# hotmetal.net
KiCad netlist of a schematic drawn in EAGLE
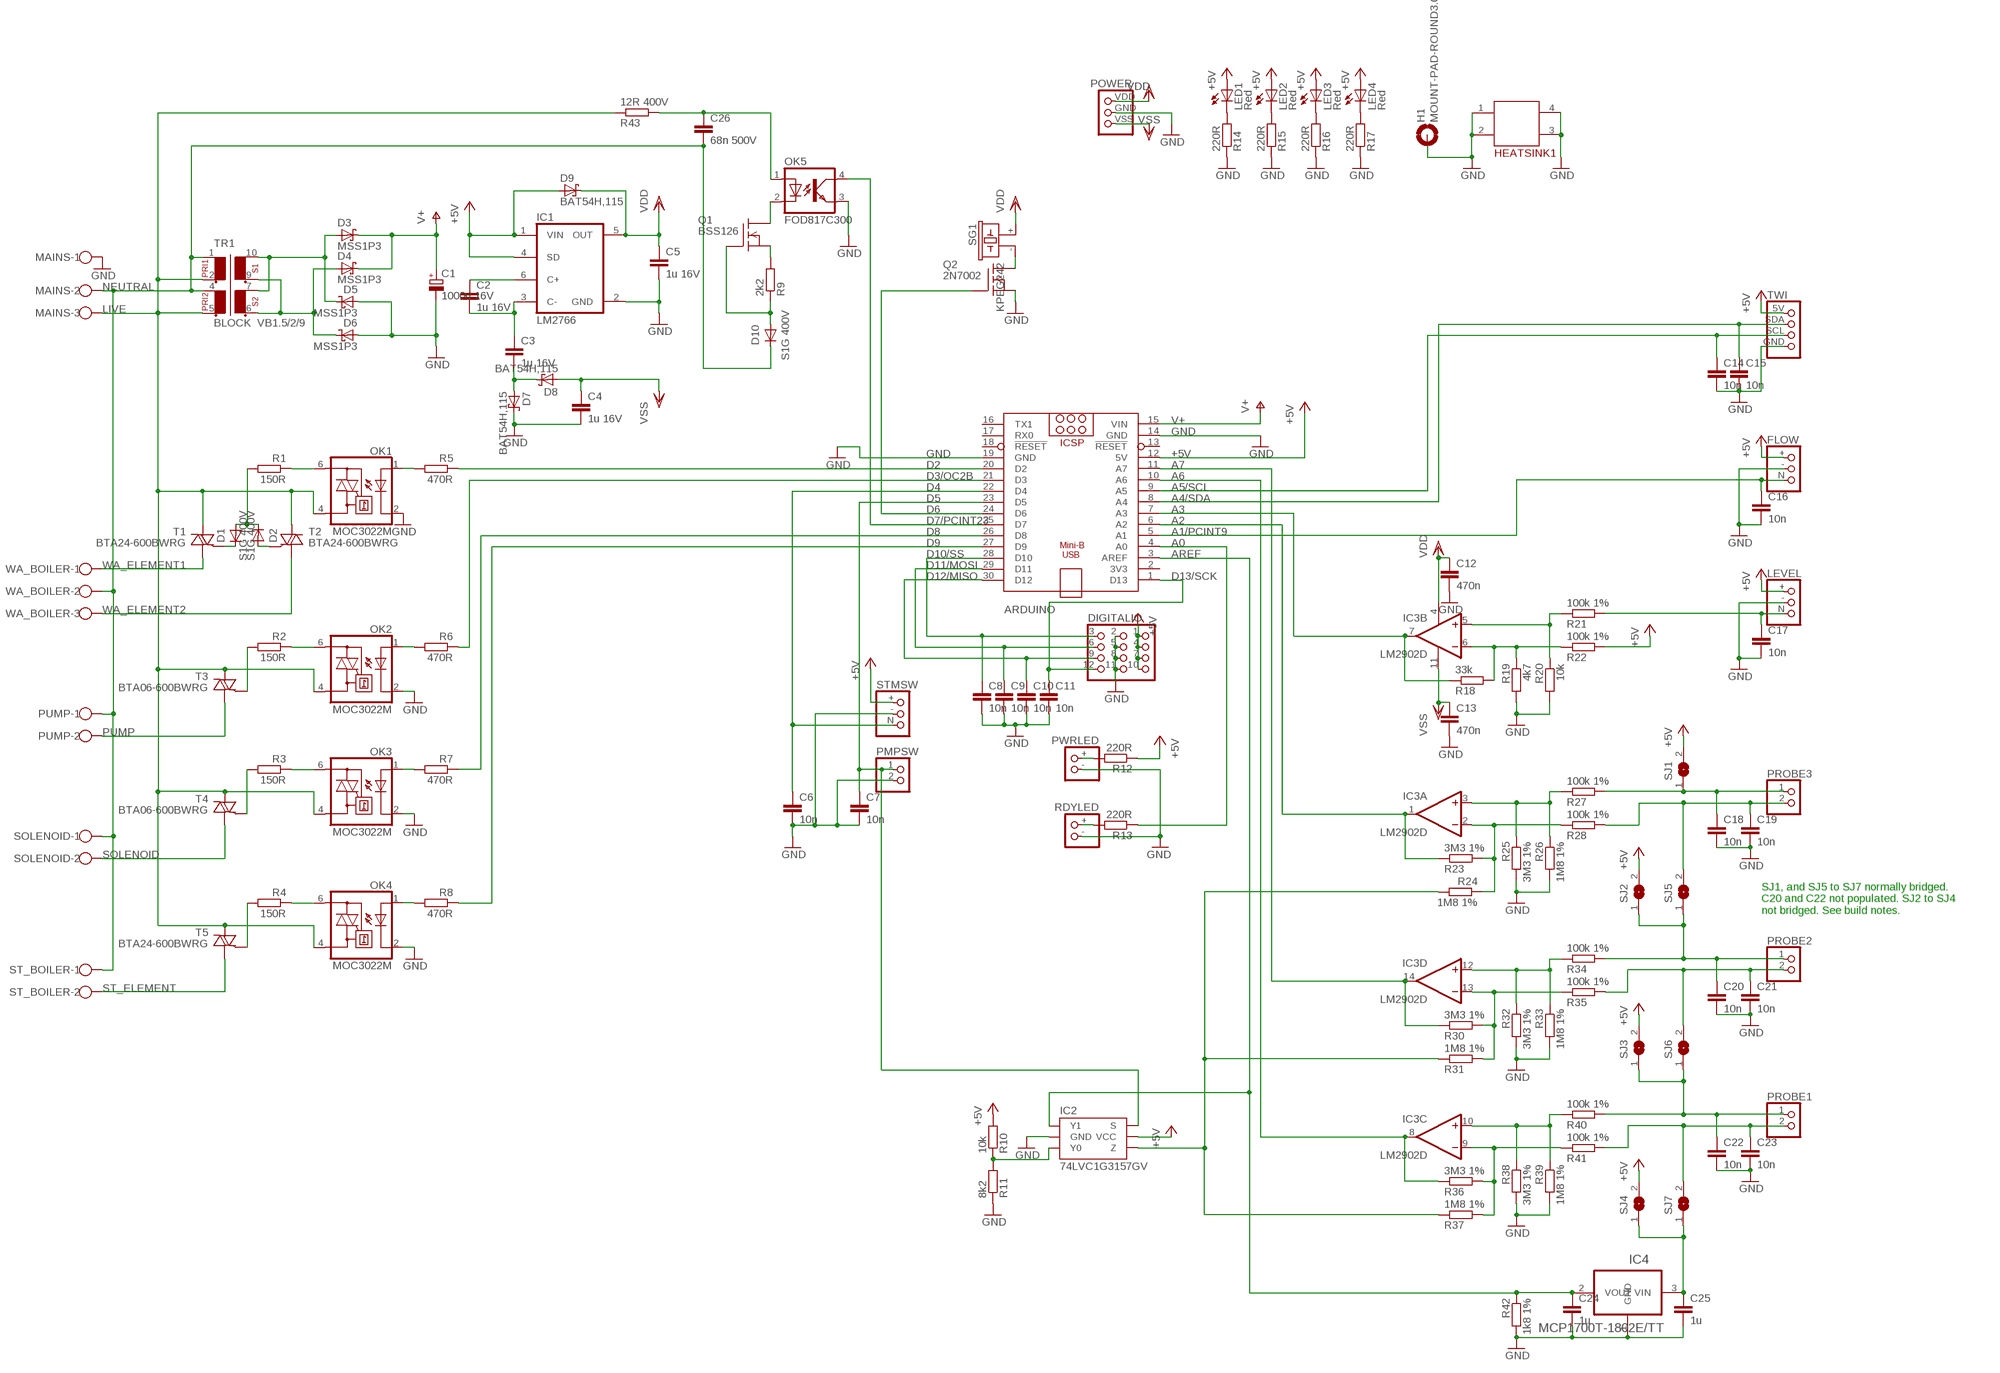
[diagram p0: schematic, sheet 1]

(export (version "E")
  (design (tool "Eeschema 10.0.6"))
  (components
    (comp (ref "ARDUINO")
      (value "ARDUINO_NANO")
      (footprint "eagle-import:ARDUINO_NANO")
      (libsource (lib "eagle-import") (part "ARDUINO_NANO"))
    )
    (comp (ref "C1")
      (value "1000u 16V")
      (footprint "eagle-import:E5-10,5")
      (libsource (lib "eagle-import") (part "CPOL-EUE5-10.5"))
    )
    (comp (ref "C2")
      (value "1u 16V")
      (footprint "eagle-import:C0603K")
      (libsource (lib "eagle-import") (part "C-EUC0603K"))
    )
    (comp (ref "C3")
      (value "1u 16V")
      (footprint "eagle-import:C0603K")
      (libsource (lib "eagle-import") (part "C-EUC0603K"))
    )
    (comp (ref "C4")
      (value "1u 16V")
      (footprint "eagle-import:C0603K")
      (libsource (lib "eagle-import") (part "C-EUC0603K"))
    )
    (comp (ref "C5")
      (value "1u 16V")
      (footprint "eagle-import:C0603K")
      (libsource (lib "eagle-import") (part "C-EUC0603K"))
    )
    (comp (ref "C6")
      (value "10n")
      (footprint "eagle-import:C0603K")
      (libsource (lib "eagle-import") (part "C-EUC0603K"))
    )
    (comp (ref "C7")
      (value "10n")
      (footprint "eagle-import:C0603K")
      (libsource (lib "eagle-import") (part "C-EUC0603K"))
    )
    (comp (ref "C8")
      (value "10n")
      (footprint "eagle-import:C0603K")
      (libsource (lib "eagle-import") (part "C-EUC0603K"))
    )
    (comp (ref "C9")
      (value "10n")
      (footprint "eagle-import:C0603K")
      (libsource (lib "eagle-import") (part "C-EUC0603K"))
    )
    (comp (ref "C10")
      (value "10n")
      (footprint "eagle-import:C0603K")
      (libsource (lib "eagle-import") (part "C-EUC0603K"))
    )
    (comp (ref "C11")
      (value "10n")
      (footprint "eagle-import:C0603K")
      (libsource (lib "eagle-import") (part "C-EUC0603K"))
    )
    (comp (ref "C12")
      (value "470n")
      (footprint "eagle-import:C0603K")
      (libsource (lib "eagle-import") (part "C-EUC0603K"))
    )
    (comp (ref "C13")
      (value "470n")
      (footprint "eagle-import:C0603K")
      (libsource (lib "eagle-import") (part "C-EUC0603K"))
    )
    (comp (ref "C14")
      (value "10n")
      (footprint "eagle-import:C0603K")
      (libsource (lib "eagle-import") (part "C-EUC0603K"))
    )
    (comp (ref "C15")
      (value "10n")
      (footprint "eagle-import:C0603K")
      (libsource (lib "eagle-import") (part "C-EUC0603K"))
    )
    (comp (ref "C16")
      (value "10n")
      (footprint "eagle-import:C0603K")
      (libsource (lib "eagle-import") (part "C-EUC0603K"))
    )
    (comp (ref "C17")
      (value "10n")
      (footprint "eagle-import:C0603K")
      (libsource (lib "eagle-import") (part "C-EUC0603K"))
    )
    (comp (ref "C18")
      (value "10n")
      (footprint "eagle-import:C0603K")
      (libsource (lib "eagle-import") (part "C-EUC0603K"))
    )
    (comp (ref "C19")
      (value "10n")
      (footprint "eagle-import:C0603K")
      (libsource (lib "eagle-import") (part "C-EUC0603K"))
    )
    (comp (ref "C20")
      (value "10n")
      (footprint "eagle-import:C0603K")
      (libsource (lib "eagle-import") (part "C-EUC0603K"))
    )
    (comp (ref "C21")
      (value "10n")
      (footprint "eagle-import:C0603K")
      (libsource (lib "eagle-import") (part "C-EUC0603K"))
    )
    (comp (ref "C22")
      (value "10n")
      (footprint "eagle-import:C0603K")
      (libsource (lib "eagle-import") (part "C-EUC0603K"))
    )
    (comp (ref "C23")
      (value "10n")
      (footprint "eagle-import:C0603K")
      (libsource (lib "eagle-import") (part "C-EUC0603K"))
    )
    (comp (ref "C24")
      (value "1u")
      (footprint "eagle-import:C0603K")
      (libsource (lib "eagle-import") (part "C-EUC0603K"))
    )
    (comp (ref "C25")
      (value "1u")
      (footprint "eagle-import:C0603K")
      (libsource (lib "eagle-import") (part "C-EUC0603K"))
    )
    (comp (ref "C26")
      (value "68n 500V")
      (footprint "eagle-import:C1210K")
      (libsource (lib "eagle-import") (part "C-EUC1210K"))
    )
    (comp (ref "D1")
      (value "S1G 400V")
      (footprint "eagle-import:DO214AC")
      (libsource (lib "eagle-import") (part "DIODE-DO214AC"))
    )
    (comp (ref "D2")
      (value "S1G 400V")
      (footprint "eagle-import:DO214AC")
      (libsource (lib "eagle-import") (part "DIODE-DO214AC"))
    )
    (comp (ref "D3")
      (value "MSS1P3")
      (footprint "eagle-import:POWERDI323")
      (libsource (lib "eagle-import") (part "PD3S160"))
    )
    (comp (ref "D4")
      (value "MSS1P3")
      (footprint "eagle-import:POWERDI323")
      (libsource (lib "eagle-import") (part "PD3S160"))
    )
    (comp (ref "D5")
      (value "MSS1P3")
      (footprint "eagle-import:POWERDI323")
      (libsource (lib "eagle-import") (part "PD3S160"))
    )
    (comp (ref "D6")
      (value "MSS1P3")
      (footprint "eagle-import:POWERDI323")
      (libsource (lib "eagle-import") (part "PD3S160"))
    )
    (comp (ref "D7")
      (value "BAT54H,115")
      (footprint "eagle-import:SOD123F")
      (libsource (lib "eagle-import") (part "BAT54H,115"))
    )
    (comp (ref "D8")
      (value "BAT54H,115")
      (footprint "eagle-import:SOD123F")
      (libsource (lib "eagle-import") (part "BAT54H,115"))
    )
    (comp (ref "D9")
      (value "BAT54H,115")
      (footprint "eagle-import:SOD123F")
      (libsource (lib "eagle-import") (part "BAT54H,115"))
    )
    (comp (ref "D10")
      (value "S1G 400V")
      (footprint "eagle-import:DO214AC")
      (libsource (lib "eagle-import") (part "DIODE-DO214AC"))
    )
    (comp (ref "DIGITALIO")
      (value "HDR4X3PWR")
      (footprint "eagle-import:HDR4X3PWR")
      (libsource (lib "eagle-import") (part "HDR4X3PWR"))
    )
    (comp (ref "FLOW")
      (value "HDR3PWR")
      (footprint "eagle-import:HDR3PWR")
      (libsource (lib "eagle-import") (part "HDR3PWR"))
    )
    (comp (ref "H1")
      (value "MOUNT-PAD-ROUND3.0")
      (footprint "eagle-import:3,0-PAD")
      (libsource (lib "eagle-import") (part "MOUNT-PAD-ROUND3.0"))
    )
    (comp (ref "HEATSINK1")
      (value "HOTMETALHEATSINK")
      (footprint "eagle-import:HOTMETALHEATSINK")
      (libsource (lib "eagle-import") (part "HOTMETALHEATSINK"))
    )
    (comp (ref "IC1")
      (value "LM2766")
      (footprint "eagle-import:SOT23-6")
      (libsource (lib "eagle-import") (part "LM2766"))
    )
    (comp (ref "IC2")
      (value "74LVC1G3157GV")
      (footprint "eagle-import:SOT457")
      (libsource (lib "eagle-import") (part "74LVC1G3157GV"))
    )
    (comp (ref "IC3")
      (value "LM2902D")
      (footprint "eagle-import:SO14")
      (libsource (lib "eagle-import") (part "LM2902D"))
    )
    (comp (ref "IC4")
      (value "MCP1700T-1802E/TT")
      (footprint "eagle-import:SOT23")
      (libsource (lib "eagle-import") (part "MCP1700T-1802E/TT"))
    )
    (comp (ref "LED1")
      (value "Red")
      (footprint "eagle-import:SML0805")
      (libsource (lib "eagle-import") (part "LEDSML0805"))
    )
    (comp (ref "LED2")
      (value "Red")
      (footprint "eagle-import:SML0805")
      (libsource (lib "eagle-import") (part "LEDSML0805"))
    )
    (comp (ref "LED3")
      (value "Red")
      (footprint "eagle-import:SML0805")
      (libsource (lib "eagle-import") (part "LEDSML0805"))
    )
    (comp (ref "LED4")
      (value "Red")
      (footprint "eagle-import:SML0805")
      (libsource (lib "eagle-import") (part "LEDSML0805"))
    )
    (comp (ref "LEVEL")
      (value "HDR3PWR")
      (footprint "eagle-import:HDR3PWR")
      (libsource (lib "eagle-import") (part "HDR3PWR"))
    )
    (comp (ref "MAINS")
      (value "W237-103")
      (footprint "eagle-import:W237-103")
      (fields (field (name "MPN") "237-103"))
      (libsource (lib "eagle-import") (part "W237-103"))
    )
    (comp (ref "OK1")
      (value "MOC3022M")
      (footprint "eagle-import:DIL06")
      (fields (field (name "MF") "FAIRCHILD SEMICONDUCTOR") (field (name "MPN") "MOC3022-M"))
      (libsource (lib "eagle-import") (part "MOC30M22"))
    )
    (comp (ref "OK2")
      (value "MOC3022M")
      (footprint "eagle-import:DIL06")
      (fields (field (name "MF") "FAIRCHILD SEMICONDUCTOR") (field (name "MPN") "MOC3022-M"))
      (libsource (lib "eagle-import") (part "MOC30M22"))
    )
    (comp (ref "OK3")
      (value "MOC3022M")
      (footprint "eagle-import:DIL06")
      (fields (field (name "MF") "FAIRCHILD SEMICONDUCTOR") (field (name "MPN") "MOC3022-M"))
      (libsource (lib "eagle-import") (part "MOC30M22"))
    )
    (comp (ref "OK4")
      (value "MOC3022M")
      (footprint "eagle-import:DIL06")
      (fields (field (name "MF") "FAIRCHILD SEMICONDUCTOR") (field (name "MPN") "MOC3022-M"))
      (libsource (lib "eagle-import") (part "MOC30M22"))
    )
    (comp (ref "OK5")
      (value "FOD817C300")
      (footprint "eagle-import:DIL04")
      (fields (field (name "MPN") "PC817X4J000F"))
      (libsource (lib "eagle-import") (part "PC817"))
    )
    (comp (ref "PMPSW")
      (value "HDR2")
      (footprint "eagle-import:HDR2")
      (libsource (lib "eagle-import") (part "HDR2"))
    )
    (comp (ref "POWER")
      (value "HDR3VDDVSS")
      (footprint "eagle-import:HDR2VDDVSS")
      (libsource (lib "eagle-import") (part "HDR3VDDVSS"))
    )
    (comp (ref "PROBE1")
      (value "HDR2")
      (footprint "eagle-import:HDR2")
      (libsource (lib "eagle-import") (part "HDR2"))
    )
    (comp (ref "PROBE2")
      (value "HDR2")
      (footprint "eagle-import:HDR2")
      (libsource (lib "eagle-import") (part "HDR2"))
    )
    (comp (ref "PROBE3")
      (value "HDR2")
      (footprint "eagle-import:HDR2")
      (libsource (lib "eagle-import") (part "HDR2"))
    )
    (comp (ref "PUMP")
      (value "W237-102")
      (footprint "eagle-import:W237-102")
      (fields (field (name "MPN") "237-102"))
      (libsource (lib "eagle-import") (part "W237-102"))
    )
    (comp (ref "PWRLED")
      (value "HDR2PWR")
      (footprint "eagle-import:HDR2PWR")
      (libsource (lib "eagle-import") (part "HDR2PWR"))
    )
    (comp (ref "Q1")
      (value "BSS126")
      (footprint "eagle-import:SOT23")
      (libsource (lib "eagle-import") (part "2N7002"))
    )
    (comp (ref "Q2")
      (value "2N7002")
      (footprint "eagle-import:SOT23")
      (libsource (lib "eagle-import") (part "2N7002"))
    )
    (comp (ref "R1")
      (value "150R")
      (footprint "eagle-import:0204_7")
      (libsource (lib "eagle-import") (part "R-EU_0204/7"))
    )
    (comp (ref "R2")
      (value "150R")
      (footprint "eagle-import:0204_7")
      (libsource (lib "eagle-import") (part "R-EU_0204/7"))
    )
    (comp (ref "R3")
      (value "150R")
      (footprint "eagle-import:0204_7")
      (libsource (lib "eagle-import") (part "R-EU_0204/7"))
    )
    (comp (ref "R4")
      (value "150R")
      (footprint "eagle-import:0204_7")
      (libsource (lib "eagle-import") (part "R-EU_0204/7"))
    )
    (comp (ref "R5")
      (value "470R")
      (footprint "eagle-import:R0805")
      (libsource (lib "eagle-import") (part "R-EU_R0805"))
    )
    (comp (ref "R6")
      (value "470R")
      (footprint "eagle-import:R0805")
      (libsource (lib "eagle-import") (part "R-EU_R0805"))
    )
    (comp (ref "R7")
      (value "470R")
      (footprint "eagle-import:R0805")
      (libsource (lib "eagle-import") (part "R-EU_R0805"))
    )
    (comp (ref "R8")
      (value "470R")
      (footprint "eagle-import:R0805")
      (libsource (lib "eagle-import") (part "R-EU_R0805"))
    )
    (comp (ref "R9")
      (value "2k2")
      (footprint "eagle-import:R0805")
      (libsource (lib "eagle-import") (part "R-EU_R0805"))
    )
    (comp (ref "R10")
      (value "10k")
      (footprint "eagle-import:R0805")
      (libsource (lib "eagle-import") (part "R-EU_R0805"))
    )
    (comp (ref "R11")
      (value "8k2")
      (footprint "eagle-import:R0805")
      (libsource (lib "eagle-import") (part "R-EU_R0805"))
    )
    (comp (ref "R12")
      (value "220R")
      (footprint "eagle-import:R0805")
      (libsource (lib "eagle-import") (part "R-EU_R0805"))
    )
    (comp (ref "R13")
      (value "220R")
      (footprint "eagle-import:R0805")
      (libsource (lib "eagle-import") (part "R-EU_R0805"))
    )
    (comp (ref "R14")
      (value "220R")
      (footprint "eagle-import:R0805")
      (libsource (lib "eagle-import") (part "R-EU_R0805"))
    )
    (comp (ref "R15")
      (value "220R")
      (footprint "eagle-import:R0805")
      (libsource (lib "eagle-import") (part "R-EU_R0805"))
    )
    (comp (ref "R16")
      (value "220R")
      (footprint "eagle-import:R0805")
      (libsource (lib "eagle-import") (part "R-EU_R0805"))
    )
    (comp (ref "R17")
      (value "220R")
      (footprint "eagle-import:R0805")
      (libsource (lib "eagle-import") (part "R-EU_R0805"))
    )
    (comp (ref "R18")
      (value "33k")
      (footprint "eagle-import:R0805")
      (libsource (lib "eagle-import") (part "R-EU_R0805"))
    )
    (comp (ref "R19")
      (value "4k7")
      (footprint "eagle-import:R0805")
      (libsource (lib "eagle-import") (part "R-EU_R0805"))
    )
    (comp (ref "R20")
      (value "10k")
      (footprint "eagle-import:R0805")
      (libsource (lib "eagle-import") (part "R-EU_R0805"))
    )
    (comp (ref "R21")
      (value "100k 1%")
      (footprint "eagle-import:R0805")
      (libsource (lib "eagle-import") (part "R-EU_R0805"))
    )
    (comp (ref "R22")
      (value "100k 1%")
      (footprint "eagle-import:R0805")
      (libsource (lib "eagle-import") (part "R-EU_R0805"))
    )
    (comp (ref "R23")
      (value "3M3 1%")
      (footprint "eagle-import:R0805")
      (libsource (lib "eagle-import") (part "R-EU_R0805"))
    )
    (comp (ref "R24")
      (value "1M8 1%")
      (footprint "eagle-import:R0805")
      (libsource (lib "eagle-import") (part "R-EU_R0805"))
    )
    (comp (ref "R25")
      (value "3M3 1%")
      (footprint "eagle-import:R0805")
      (libsource (lib "eagle-import") (part "R-EU_R0805"))
    )
    (comp (ref "R26")
      (value "1M8 1%")
      (footprint "eagle-import:R0805")
      (libsource (lib "eagle-import") (part "R-EU_R0805"))
    )
    (comp (ref "R27")
      (value "100k 1%")
      (footprint "eagle-import:R0805")
      (libsource (lib "eagle-import") (part "R-EU_R0805"))
    )
    (comp (ref "R28")
      (value "100k 1%")
      (footprint "eagle-import:R0805")
      (libsource (lib "eagle-import") (part "R-EU_R0805"))
    )
    (comp (ref "R30")
      (value "3M3 1%")
      (footprint "eagle-import:R0805")
      (libsource (lib "eagle-import") (part "R-EU_R0805"))
    )
    (comp (ref "R31")
      (value "1M8 1%")
      (footprint "eagle-import:R0805")
      (libsource (lib "eagle-import") (part "R-EU_R0805"))
    )
    (comp (ref "R32")
      (value "3M3 1%")
      (footprint "eagle-import:R0805")
      (libsource (lib "eagle-import") (part "R-EU_R0805"))
    )
    (comp (ref "R33")
      (value "1M8 1%")
      (footprint "eagle-import:R0805")
      (libsource (lib "eagle-import") (part "R-EU_R0805"))
    )
    (comp (ref "R34")
      (value "100k 1%")
      (footprint "eagle-import:R0805")
      (libsource (lib "eagle-import") (part "R-EU_R0805"))
    )
    (comp (ref "R35")
      (value "100k 1%")
      (footprint "eagle-import:R0805")
      (libsource (lib "eagle-import") (part "R-EU_R0805"))
    )
    (comp (ref "R36")
      (value "3M3 1%")
      (footprint "eagle-import:R0805")
      (libsource (lib "eagle-import") (part "R-EU_R0805"))
    )
    (comp (ref "R37")
      (value "1M8 1%")
      (footprint "eagle-import:R0805")
      (libsource (lib "eagle-import") (part "R-EU_R0805"))
    )
    (comp (ref "R38")
      (value "3M3 1%")
      (footprint "eagle-import:R0805")
      (libsource (lib "eagle-import") (part "R-EU_R0805"))
    )
    (comp (ref "R39")
      (value "1M8 1%")
      (footprint "eagle-import:R0805")
      (libsource (lib "eagle-import") (part "R-EU_R0805"))
    )
    (comp (ref "R40")
      (value "100k 1%")
      (footprint "eagle-import:R0805")
      (libsource (lib "eagle-import") (part "R-EU_R0805"))
    )
    (comp (ref "R41")
      (value "100k 1%")
      (footprint "eagle-import:R0805")
      (libsource (lib "eagle-import") (part "R-EU_R0805"))
    )
    (comp (ref "R42")
      (value "1k8 1%")
      (footprint "eagle-import:R0805")
      (libsource (lib "eagle-import") (part "R-EU_R0805"))
    )
    (comp (ref "R43")
      (value "12R 400V")
      (footprint "eagle-import:R0805")
      (libsource (lib "eagle-import") (part "R-EU_R0805"))
    )
    (comp (ref "RDYLED")
      (value "HDR2PWR")
      (footprint "eagle-import:HDR2PWR")
      (libsource (lib "eagle-import") (part "HDR2PWR"))
    )
    (comp (ref "SG1")
      (value "KPEG242")
      (footprint "eagle-import:F_CM12P")
      (libsource (lib "eagle-import") (part "F/CM12P"))
    )
    (comp (ref "SJ1") (value "SJ") (footprint "eagle-import:SJ") (libsource (lib "eagle-import") (part "SJ")))
    (comp (ref "SJ2") (value "SJ") (footprint "eagle-import:SJ") (libsource (lib "eagle-import") (part "SJ")))
    (comp (ref "SJ3") (value "SJ") (footprint "eagle-import:SJ") (libsource (lib "eagle-import") (part "SJ")))
    (comp (ref "SJ4") (value "SJ") (footprint "eagle-import:SJ") (libsource (lib "eagle-import") (part "SJ")))
    (comp (ref "SJ5") (value "SJ") (footprint "eagle-import:SJ") (libsource (lib "eagle-import") (part "SJ")))
    (comp (ref "SJ6") (value "SJ") (footprint "eagle-import:SJ") (libsource (lib "eagle-import") (part "SJ")))
    (comp (ref "SJ7") (value "SJ") (footprint "eagle-import:SJ") (libsource (lib "eagle-import") (part "SJ")))
    (comp (ref "SOLENOID")
      (value "W237-102")
      (footprint "eagle-import:W237-102")
      (fields (field (name "MPN") "237-102"))
      (libsource (lib "eagle-import") (part "W237-102"))
    )
    (comp (ref "STMSW")
      (value "HDR3PWR")
      (footprint "eagle-import:HDR3PWR")
      (libsource (lib "eagle-import") (part "HDR3PWR"))
    )
    (comp (ref "ST_BOILER")
      (value "W237-102")
      (footprint "eagle-import:W237-102")
      (fields (field (name "MPN") "237-102"))
      (libsource (lib "eagle-import") (part "W237-102"))
    )
    (comp (ref "T1")
      (value "BTA24-600BWRG")
      (footprint "eagle-import:TO220FACEDOWN")
      (libsource (lib "eagle-import") (part "BTA_TRIAC"))
    )
    (comp (ref "T2")
      (value "BTA24-600BWRG")
      (footprint "eagle-import:TO220FACEDOWN")
      (libsource (lib "eagle-import") (part "BTA_TRIAC"))
    )
    (comp (ref "T3")
      (value "BTA06-600BWRG")
      (footprint "eagle-import:TO220FACEDOWN")
      (libsource (lib "eagle-import") (part "BTA_TRIAC"))
    )
    (comp (ref "T4")
      (value "BTA06-600BWRG")
      (footprint "eagle-import:TO220FACEDOWN")
      (libsource (lib "eagle-import") (part "BTA_TRIAC"))
    )
    (comp (ref "T5")
      (value "BTA24-600BWRG")
      (footprint "eagle-import:TO220FACEDOWN")
      (libsource (lib "eagle-import") (part "BTA_TRIAC"))
    )
    (comp (ref "TR1")
      (value "BLOCK VB1.5/2/9")
      (footprint "eagle-import:T2P2S")
      (libsource (lib "eagle-import") (part "TRAFO20X20MM2P2S"))
    )
    (comp (ref "TWI")
      (value "HDR4TWI")
      (footprint "eagle-import:HDR4TWI")
      (libsource (lib "eagle-import") (part "HDR4TWI"))
    )
    (comp (ref "WA_BOILER")
      (value "W237-103")
      (footprint "eagle-import:W237-103")
      (fields (field (name "MPN") "237-103"))
      (libsource (lib "eagle-import") (part "W237-103"))
    )
  )
  (nets
    (net (code "1") (name "+5V") (class "Default")
      (node (ref "ARDUINO") (pin "12") (pinfunction "5V_12") (pintype "power_in"))
      (node (ref "D9") (pin "A") (pinfunction "A_A") (pintype "passive"))
      (node (ref "DIGITALIO") (pin "1") (pinfunction "1_1") (pintype "passive"))
      (node (ref "DIGITALIO") (pin "10") (pinfunction "10_10") (pintype "passive"))
      (node (ref "DIGITALIO") (pin "4") (pinfunction "4_4") (pintype "passive"))
      (node (ref "DIGITALIO") (pin "7") (pinfunction "7_7") (pintype "passive"))
      (node (ref "FLOW") (pin "+") (pinfunction "1_+") (pintype "passive"))
      (node (ref "IC1") (pin "1") (pinfunction "VIN_1") (pintype "power_in"))
      (node (ref "IC1") (pin "4") (pinfunction "SD_4") (pintype "input"))
      (node (ref "IC2") (pin "5") (pinfunction "VCC_5") (pintype "power_in"))
      (node (ref "LED1") (pin "A") (pinfunction "A_A") (pintype "passive"))
      (node (ref "LED2") (pin "A") (pinfunction "A_A") (pintype "passive"))
      (node (ref "LED3") (pin "A") (pinfunction "A_A") (pintype "passive"))
      (node (ref "LED4") (pin "A") (pinfunction "A_A") (pintype "passive"))
      (node (ref "LEVEL") (pin "+") (pinfunction "1_+") (pintype "passive"))
      (node (ref "R10") (pin "2") (pinfunction "2_2") (pintype "passive"))
      (node (ref "R12") (pin "1") (pinfunction "1_1") (pintype "passive"))
      (node (ref "R22") (pin "2") (pinfunction "2_2") (pintype "passive"))
      (node (ref "SJ1") (pin "2") (pinfunction "2_2") (pintype "passive"))
      (node (ref "SJ2") (pin "2") (pinfunction "2_2") (pintype "passive"))
      (node (ref "SJ3") (pin "2") (pinfunction "2_2") (pintype "passive"))
      (node (ref "SJ4") (pin "2") (pinfunction "2_2") (pintype "passive"))
      (node (ref "STMSW") (pin "+") (pinfunction "1_+") (pintype "passive"))
      (node (ref "TWI") (pin "5V") (pinfunction "1_5V") (pintype "passive"))
    )
    (net (code "2") (name "/A0") (class "Default")
      (node (ref "ARDUINO") (pin "4") (pinfunction "A0_4") (pintype "bidirectional"))
      (node (ref "R13") (pin "1") (pinfunction "1_1") (pintype "passive"))
    )
    (net (code "3") (name "/A1{slash}PCINT9") (class "Default")
      (node (ref "ARDUINO") (pin "5") (pinfunction "A1_5") (pintype "bidirectional"))
      (node (ref "C16") (pin "1") (pinfunction "1_1") (pintype "passive"))
      (node (ref "FLOW") (pin "N") (pinfunction "3_N") (pintype "passive"))
    )
    (net (code "4") (name "/A2") (class "Default")
      (node (ref "ARDUINO") (pin "6") (pinfunction "A2_6") (pintype "bidirectional"))
      (node (ref "IC3") (pin "1") (pinfunction "OUT_1") (pintype "output"))
      (node (ref "R23") (pin "1") (pinfunction "1_1") (pintype "passive"))
    )
    (net (code "5") (name "/A3") (class "Default")
      (node (ref "ARDUINO") (pin "7") (pinfunction "A3_7") (pintype "bidirectional"))
      (node (ref "IC3") (pin "7") (pinfunction "OUT_7") (pintype "output"))
      (node (ref "R18") (pin "1") (pinfunction "1_1") (pintype "passive"))
    )
    (net (code "6") (name "/A4{slash}SDA") (class "Default")
      (node (ref "ARDUINO") (pin "8") (pinfunction "A4_8") (pintype "bidirectional"))
      (node (ref "C15") (pin "1") (pinfunction "1_1") (pintype "passive"))
      (node (ref "TWI") (pin "SDA") (pinfunction "2_SDA") (pintype "passive"))
    )
    (net (code "7") (name "/A5{slash}SCL") (class "Default")
      (node (ref "ARDUINO") (pin "9") (pinfunction "A5_9") (pintype "bidirectional"))
      (node (ref "C14") (pin "1") (pinfunction "1_1") (pintype "passive"))
      (node (ref "TWI") (pin "SCL") (pinfunction "3_SCL") (pintype "passive"))
    )
    (net (code "8") (name "/A6") (class "Default")
      (node (ref "ARDUINO") (pin "10") (pinfunction "A6_10") (pintype "bidirectional"))
      (node (ref "IC3") (pin "8") (pinfunction "OUT_8") (pintype "output"))
      (node (ref "R36") (pin "1") (pinfunction "1_1") (pintype "passive"))
    )
    (net (code "9") (name "/A7") (class "Default")
      (node (ref "ARDUINO") (pin "11") (pinfunction "A7_11") (pintype "bidirectional"))
      (node (ref "IC3") (pin "14") (pinfunction "OUT_14") (pintype "output"))
      (node (ref "R30") (pin "1") (pinfunction "1_1") (pintype "passive"))
    )
    (net (code "10") (name "/AREF") (class "Default")
      (node (ref "ARDUINO") (pin "3") (pinfunction "AREF_3") (pintype "input"))
      (node (ref "C24") (pin "1") (pinfunction "1_1") (pintype "passive"))
      (node (ref "IC2") (pin "1") (pinfunction "Y1_1") (pintype "bidirectional"))
      (node (ref "IC4") (pin "2") (pinfunction "VOUT_2") (pintype "output"))
      (node (ref "R42") (pin "1") (pinfunction "1_1") (pintype "passive"))
    )
    (net (code "11") (name "/D2") (class "Default")
      (node (ref "ARDUINO") (pin "20") (pinfunction "D2_20") (pintype "bidirectional"))
      (node (ref "R5") (pin "1") (pinfunction "1_1") (pintype "passive"))
    )
    (net (code "12") (name "/D3{slash}OC2B") (class "Default")
      (node (ref "ARDUINO") (pin "21") (pinfunction "D3_21") (pintype "bidirectional"))
      (node (ref "R6") (pin "1") (pinfunction "1_1") (pintype "passive"))
    )
    (net (code "13") (name "/D4") (class "Default")
      (node (ref "ARDUINO") (pin "22") (pinfunction "D4_22") (pintype "bidirectional"))
      (node (ref "C6") (pin "1") (pinfunction "1_1") (pintype "passive"))
      (node (ref "STMSW") (pin "N") (pinfunction "3_N") (pintype "passive"))
    )
    (net (code "14") (name "/D5") (class "Default")
      (node (ref "ARDUINO") (pin "23") (pinfunction "D5_23") (pintype "bidirectional"))
      (node (ref "C7") (pin "1") (pinfunction "1_1") (pintype "passive"))
      (node (ref "IC2") (pin "6") (pinfunction "S_6") (pintype "bidirectional"))
      (node (ref "PMPSW") (pin "1") (pinfunction "1_1") (pintype "passive"))
    )
    (net (code "15") (name "/D6") (class "Default")
      (node (ref "ARDUINO") (pin "24") (pinfunction "D6_24") (pintype "bidirectional"))
      (node (ref "Q2") (pin "1") (pinfunction "G_1") (pintype "passive"))
    )
    (net (code "16") (name "/D7{slash}PCINT23") (class "Default")
      (node (ref "ARDUINO") (pin "25") (pinfunction "D7_25") (pintype "bidirectional"))
      (node (ref "OK5") (pin "4") (pinfunction "COL_4") (pintype "passive"))
    )
    (net (code "17") (name "/D8") (class "Default")
      (node (ref "ARDUINO") (pin "26") (pinfunction "D8_26") (pintype "bidirectional"))
      (node (ref "R7") (pin "1") (pinfunction "1_1") (pintype "passive"))
    )
    (net (code "18") (name "/D9") (class "Default")
      (node (ref "ARDUINO") (pin "27") (pinfunction "D9_27") (pintype "bidirectional"))
      (node (ref "R8") (pin "1") (pinfunction "1_1") (pintype "passive"))
    )
    (net (code "19") (name "/D10{slash}SS") (class "Default")
      (node (ref "ARDUINO") (pin "28") (pinfunction "D10_28") (pintype "bidirectional"))
      (node (ref "C8") (pin "1") (pinfunction "1_1") (pintype "passive"))
      (node (ref "DIGITALIO") (pin "3") (pinfunction "3_3") (pintype "passive"))
    )
    (net (code "20") (name "/D11{slash}MOSI") (class "Default")
      (node (ref "ARDUINO") (pin "29") (pinfunction "D11_29") (pintype "bidirectional"))
      (node (ref "C9") (pin "1") (pinfunction "1_1") (pintype "passive"))
      (node (ref "DIGITALIO") (pin "6") (pinfunction "6_6") (pintype "passive"))
    )
    (net (code "21") (name "/D12{slash}MISO") (class "Default")
      (node (ref "ARDUINO") (pin "30") (pinfunction "D12_30") (pintype "bidirectional"))
      (node (ref "C10") (pin "1") (pinfunction "1_1") (pintype "passive"))
      (node (ref "DIGITALIO") (pin "9") (pinfunction "9_9") (pintype "passive"))
    )
    (net (code "22") (name "/D13{slash}SCK") (class "Default")
      (node (ref "ARDUINO") (pin "1") (pinfunction "D13_1") (pintype "bidirectional"))
      (node (ref "C11") (pin "1") (pinfunction "1_1") (pintype "passive"))
      (node (ref "DIGITALIO") (pin "12") (pinfunction "12_12") (pintype "passive"))
    )
    (net (code "23") (name "/LIVE") (class "Default")
      (node (ref "MAINS") (pin "3") (pinfunction "KL_3") (pintype "passive"))
      (node (ref "OK1") (pin "4") (pinfunction "A1_4") (pintype "passive"))
      (node (ref "OK2") (pin "4") (pinfunction "A1_4") (pintype "passive"))
      (node (ref "OK3") (pin "4") (pinfunction "A1_4") (pintype "passive"))
      (node (ref "OK4") (pin "4") (pinfunction "A1_4") (pintype "passive"))
      (node (ref "R43") (pin "1") (pinfunction "1_1") (pintype "passive"))
      (node (ref "T1") (pin "T2") (pinfunction "A2_T2") (pintype "passive"))
      (node (ref "T2") (pin "T2") (pinfunction "A2_T2") (pintype "passive"))
      (node (ref "T3") (pin "T2") (pinfunction "A2_T2") (pintype "passive"))
      (node (ref "T4") (pin "T2") (pinfunction "A2_T2") (pintype "passive"))
      (node (ref "T5") (pin "T2") (pinfunction "A2_T2") (pintype "passive"))
      (node (ref "TR1") (pin "2") (pinfunction "2_2") (pintype "passive"))
      (node (ref "TR1") (pin "5") (pinfunction "5_5") (pintype "passive"))
    )
    (net (code "24") (name "/NEUTRAL") (class "Default")
      (node (ref "C26") (pin "2") (pinfunction "2_2") (pintype "passive"))
      (node (ref "D10") (pin "C") (pinfunction "C_C") (pintype "passive"))
      (node (ref "MAINS") (pin "2") (pinfunction "KL_2") (pintype "passive"))
      (node (ref "PUMP") (pin "1") (pinfunction "KL_1") (pintype "passive"))
      (node (ref "SOLENOID") (pin "1") (pinfunction "KL_1") (pintype "passive"))
      (node (ref "ST_BOILER") (pin "1") (pinfunction "KL_1") (pintype "passive"))
      (node (ref "TR1") (pin "1") (pinfunction "1_1") (pintype "passive"))
      (node (ref "TR1") (pin "4") (pinfunction "4_4") (pintype "passive"))
      (node (ref "WA_BOILER") (pin "2") (pinfunction "KL_2") (pintype "passive"))
    )
    (net (code "25") (name "/PUMP") (class "Default")
      (node (ref "PUMP") (pin "2") (pinfunction "KL_2") (pintype "passive"))
      (node (ref "T3") (pin "T1") (pinfunction "A1_T1") (pintype "passive"))
    )
    (net (code "26") (name "/SOLENOID") (class "Default")
      (node (ref "SOLENOID") (pin "2") (pinfunction "KL_2") (pintype "passive"))
      (node (ref "T4") (pin "T1") (pinfunction "A1_T1") (pintype "passive"))
    )
    (net (code "27") (name "/ST_ELEMENT") (class "Default")
      (node (ref "ST_BOILER") (pin "2") (pinfunction "KL_2") (pintype "passive"))
      (node (ref "T5") (pin "T1") (pinfunction "A1_T1") (pintype "passive"))
    )
    (net (code "28") (name "/WA_ELEMENT1") (class "Default")
      (node (ref "T1") (pin "T1") (pinfunction "A1_T1") (pintype "passive"))
      (node (ref "WA_BOILER") (pin "1") (pinfunction "KL_1") (pintype "passive"))
    )
    (net (code "29") (name "/WA_ELEMENT2") (class "Default")
      (node (ref "T2") (pin "T1") (pinfunction "A1_T1") (pintype "passive"))
      (node (ref "WA_BOILER") (pin "3") (pinfunction "KL_3") (pintype "passive"))
    )
    (net (code "30") (name "GND") (class "Default")
      (node (ref "ARDUINO") (pin "14") (pinfunction "GND_14") (pintype "power_in"))
      (node (ref "ARDUINO") (pin "19") (pinfunction "GND_19") (pintype "power_in"))
      (node (ref "C1") (pin "-") (pinfunction "-_-") (pintype "passive"))
      (node (ref "C10") (pin "2") (pinfunction "2_2") (pintype "passive"))
      (node (ref "C11") (pin "2") (pinfunction "2_2") (pintype "passive"))
      (node (ref "C12") (pin "2") (pinfunction "2_2") (pintype "passive"))
      (node (ref "C13") (pin "2") (pinfunction "2_2") (pintype "passive"))
      (node (ref "C14") (pin "2") (pinfunction "2_2") (pintype "passive"))
      (node (ref "C15") (pin "2") (pinfunction "2_2") (pintype "passive"))
      (node (ref "C16") (pin "2") (pinfunction "2_2") (pintype "passive"))
      (node (ref "C17") (pin "2") (pinfunction "2_2") (pintype "passive"))
      (node (ref "C18") (pin "2") (pinfunction "2_2") (pintype "passive"))
      (node (ref "C19") (pin "2") (pinfunction "2_2") (pintype "passive"))
      (node (ref "C20") (pin "2") (pinfunction "2_2") (pintype "passive"))
      (node (ref "C21") (pin "2") (pinfunction "2_2") (pintype "passive"))
      (node (ref "C22") (pin "2") (pinfunction "2_2") (pintype "passive"))
      (node (ref "C23") (pin "2") (pinfunction "2_2") (pintype "passive"))
      (node (ref "C24") (pin "2") (pinfunction "2_2") (pintype "passive"))
      (node (ref "C25") (pin "2") (pinfunction "2_2") (pintype "passive"))
      (node (ref "C4") (pin "2") (pinfunction "2_2") (pintype "passive"))
      (node (ref "C5") (pin "2") (pinfunction "2_2") (pintype "passive"))
      (node (ref "C6") (pin "2") (pinfunction "2_2") (pintype "passive"))
      (node (ref "C7") (pin "2") (pinfunction "2_2") (pintype "passive"))
      (node (ref "C8") (pin "2") (pinfunction "2_2") (pintype "passive"))
      (node (ref "C9") (pin "2") (pinfunction "2_2") (pintype "passive"))
      (node (ref "D5") (pin "A") (pinfunction "A_A") (pintype "passive"))
      (node (ref "D6") (pin "A") (pinfunction "A_A") (pintype "passive"))
      (node (ref "D7") (pin "C") (pinfunction "C_C") (pintype "passive"))
      (node (ref "DIGITALIO") (pin "11") (pinfunction "11_11") (pintype "passive"))
      (node (ref "DIGITALIO") (pin "2") (pinfunction "2_2") (pintype "passive"))
      (node (ref "DIGITALIO") (pin "5") (pinfunction "5_5") (pintype "passive"))
      (node (ref "DIGITALIO") (pin "8") (pinfunction "8_8") (pintype "passive"))
      (node (ref "FLOW") (pin "-") (pinfunction "2_-") (pintype "passive"))
      (node (ref "H1") (pin "B3,0") (pinfunction "MOUNT_B3,0") (pintype "passive"))
      (node (ref "HEATSINK1") (pin "1") (pinfunction "P$1_1") (pintype "power_in"))
      (node (ref "HEATSINK1") (pin "2") (pinfunction "P$2_2") (pintype "power_in"))
      (node (ref "HEATSINK1") (pin "3") (pinfunction "P$3_3") (pintype "power_in"))
      (node (ref "HEATSINK1") (pin "4") (pinfunction "P$4_4") (pintype "power_in"))
      (node (ref "IC1") (pin "2") (pinfunction "GND_2") (pintype "power_in"))
      (node (ref "IC2") (pin "2") (pinfunction "GND_2") (pintype "power_in"))
      (node (ref "IC4") (pin "1") (pinfunction "GND_1") (pintype "passive"))
      (node (ref "LEVEL") (pin "-") (pinfunction "2_-") (pintype "passive"))
      (node (ref "MAINS") (pin "1") (pinfunction "KL_1") (pintype "passive"))
      (node (ref "OK1") (pin "2") (pinfunction "C_2") (pintype "passive"))
      (node (ref "OK2") (pin "2") (pinfunction "C_2") (pintype "passive"))
      (node (ref "OK3") (pin "2") (pinfunction "C_2") (pintype "passive"))
      (node (ref "OK4") (pin "2") (pinfunction "C_2") (pintype "passive"))
      (node (ref "OK5") (pin "3") (pinfunction "EMIT_3") (pintype "passive"))
      (node (ref "PMPSW") (pin "2") (pinfunction "2_2") (pintype "passive"))
      (node (ref "POWER") (pin "GND") (pinfunction "2_GND") (pintype "passive"))
      (node (ref "PWRLED") (pin "-") (pinfunction "2_-") (pintype "passive"))
      (node (ref "Q2") (pin "2") (pinfunction "S_2") (pintype "passive"))
      (node (ref "R11") (pin "1") (pinfunction "1_1") (pintype "passive"))
      (node (ref "R14") (pin "1") (pinfunction "1_1") (pintype "passive"))
      (node (ref "R15") (pin "1") (pinfunction "1_1") (pintype "passive"))
      (node (ref "R16") (pin "1") (pinfunction "1_1") (pintype "passive"))
      (node (ref "R17") (pin "1") (pinfunction "1_1") (pintype "passive"))
      (node (ref "R19") (pin "2") (pinfunction "2_2") (pintype "passive"))
      (node (ref "R20") (pin "2") (pinfunction "2_2") (pintype "passive"))
      (node (ref "R25") (pin "2") (pinfunction "2_2") (pintype "passive"))
      (node (ref "R26") (pin "2") (pinfunction "2_2") (pintype "passive"))
      (node (ref "R32") (pin "2") (pinfunction "2_2") (pintype "passive"))
      (node (ref "R33") (pin "2") (pinfunction "2_2") (pintype "passive"))
      (node (ref "R38") (pin "2") (pinfunction "2_2") (pintype "passive"))
      (node (ref "R39") (pin "2") (pinfunction "2_2") (pintype "passive"))
      (node (ref "R42") (pin "2") (pinfunction "2_2") (pintype "passive"))
      (node (ref "RDYLED") (pin "-") (pinfunction "2_-") (pintype "passive"))
      (node (ref "STMSW") (pin "-") (pinfunction "2_-") (pintype "passive"))
      (node (ref "TWI") (pin "GND") (pinfunction "4_GND") (pintype "passive"))
    )
    (net (code "31") (name "Net-(C3-Pad2)") (class "Default")
      (node (ref "C3") (pin "2") (pinfunction "2_2") (pintype "passive"))
      (node (ref "D7") (pin "A") (pinfunction "A_A") (pintype "passive"))
      (node (ref "D8") (pin "C") (pinfunction "C_C") (pintype "passive"))
    )
    (net (code "32") (name "Net-(C18-Pad1)") (class "Default")
      (node (ref "C18") (pin "1") (pinfunction "1_1") (pintype "passive"))
      (node (ref "PROBE3") (pin "1") (pinfunction "1_1") (pintype "passive"))
      (node (ref "R27") (pin "2") (pinfunction "2_2") (pintype "passive"))
      (node (ref "SJ1") (pin "1") (pinfunction "1_1") (pintype "passive"))
    )
    (net (code "33") (name "Net-(C19-Pad1)") (class "Default")
      (node (ref "C19") (pin "1") (pinfunction "1_1") (pintype "passive"))
      (node (ref "PROBE3") (pin "2") (pinfunction "2_2") (pintype "passive"))
      (node (ref "R28") (pin "2") (pinfunction "2_2") (pintype "passive"))
      (node (ref "SJ5") (pin "2") (pinfunction "2_2") (pintype "passive"))
    )
    (net (code "34") (name "Net-(C20-Pad1)") (class "Default")
      (node (ref "C20") (pin "1") (pinfunction "1_1") (pintype "passive"))
      (node (ref "PROBE2") (pin "1") (pinfunction "1_1") (pintype "passive"))
      (node (ref "R34") (pin "2") (pinfunction "2_2") (pintype "passive"))
      (node (ref "SJ2") (pin "1") (pinfunction "1_1") (pintype "passive"))
      (node (ref "SJ5") (pin "1") (pinfunction "1_1") (pintype "passive"))
    )
    (net (code "35") (name "Net-(C21-Pad1)") (class "Default")
      (node (ref "C21") (pin "1") (pinfunction "1_1") (pintype "passive"))
      (node (ref "PROBE2") (pin "2") (pinfunction "2_2") (pintype "passive"))
      (node (ref "R35") (pin "2") (pinfunction "2_2") (pintype "passive"))
      (node (ref "SJ6") (pin "2") (pinfunction "2_2") (pintype "passive"))
    )
    (net (code "36") (name "Net-(C22-Pad1)") (class "Default")
      (node (ref "C22") (pin "1") (pinfunction "1_1") (pintype "passive"))
      (node (ref "PROBE1") (pin "1") (pinfunction "1_1") (pintype "passive"))
      (node (ref "R40") (pin "2") (pinfunction "2_2") (pintype "passive"))
      (node (ref "SJ3") (pin "1") (pinfunction "1_1") (pintype "passive"))
      (node (ref "SJ6") (pin "1") (pinfunction "1_1") (pintype "passive"))
    )
    (net (code "37") (name "Net-(C23-Pad1)") (class "Default")
      (node (ref "C23") (pin "1") (pinfunction "1_1") (pintype "passive"))
      (node (ref "PROBE1") (pin "2") (pinfunction "2_2") (pintype "passive"))
      (node (ref "R41") (pin "2") (pinfunction "2_2") (pintype "passive"))
      (node (ref "SJ7") (pin "2") (pinfunction "2_2") (pintype "passive"))
    )
    (net (code "38") (name "Net-(D1-PadA)") (class "Default")
      (node (ref "D1") (pin "A") (pinfunction "A_A") (pintype "passive"))
      (node (ref "D2") (pin "C") (pinfunction "C_C") (pintype "passive"))
      (node (ref "R1") (pin "2") (pinfunction "2_2") (pintype "passive"))
    )
    (net (code "39") (name "Net-(D1-PadC)") (class "Default")
      (node (ref "D1") (pin "C") (pinfunction "C_C") (pintype "passive"))
      (node (ref "T1") (pin "G") (pinfunction "G_G") (pintype "passive"))
    )
    (net (code "40") (name "Net-(D2-PadA)") (class "Default")
      (node (ref "D2") (pin "A") (pinfunction "A_A") (pintype "passive"))
      (node (ref "T2") (pin "G") (pinfunction "G_G") (pintype "passive"))
    )
    (net (code "41") (name "Net-(D3-PadA)") (class "Default")
      (node (ref "D3") (pin "A") (pinfunction "A_A") (pintype "passive"))
      (node (ref "D5") (pin "C") (pinfunction "C_C") (pintype "passive"))
      (node (ref "TR1") (pin "10") (pinfunction "10_10") (pintype "passive"))
      (node (ref "TR1") (pin "7") (pinfunction "7_7") (pintype "passive"))
    )
    (net (code "42") (name "Net-(D4-PadA)") (class "Default")
      (node (ref "D4") (pin "A") (pinfunction "A_A") (pintype "passive"))
      (node (ref "D6") (pin "C") (pinfunction "C_C") (pintype "passive"))
      (node (ref "TR1") (pin "6") (pinfunction "6_6") (pintype "passive"))
      (node (ref "TR1") (pin "9") (pinfunction "9_9") (pintype "passive"))
    )
    (net (code "43") (name "Net-(IC1-C+)") (class "Default")
      (node (ref "C2") (pin "1") (pinfunction "1_1") (pintype "passive"))
      (node (ref "IC1") (pin "6") (pinfunction "C+_6") (pintype "passive"))
    )
    (net (code "44") (name "Net-(IC1-C-)") (class "Default")
      (node (ref "C2") (pin "2") (pinfunction "2_2") (pintype "passive"))
      (node (ref "C3") (pin "1") (pinfunction "1_1") (pintype "passive"))
      (node (ref "IC1") (pin "3") (pinfunction "C-_3") (pintype "passive"))
    )
    (net (code "45") (name "Net-(IC2-Y0)") (class "Default")
      (node (ref "IC2") (pin "3") (pinfunction "Y0_3") (pintype "bidirectional"))
      (node (ref "R10") (pin "1") (pinfunction "1_1") (pintype "passive"))
      (node (ref "R11") (pin "2") (pinfunction "2_2") (pintype "passive"))
    )
    (net (code "46") (name "Net-(IC2-Z)") (class "Default")
      (node (ref "IC2") (pin "4") (pinfunction "Z_4") (pintype "bidirectional"))
      (node (ref "R24") (pin "2") (pinfunction "2_2") (pintype "passive"))
      (node (ref "R31") (pin "1") (pinfunction "1_1") (pintype "passive"))
      (node (ref "R37") (pin "1") (pinfunction "1_1") (pintype "passive"))
    )
    (net (code "47") (name "Net-(IC3A-+IN)") (class "Default")
      (node (ref "IC3") (pin "3") (pinfunction "+IN_3") (pintype "input"))
      (node (ref "R25") (pin "1") (pinfunction "1_1") (pintype "passive"))
      (node (ref "R26") (pin "1") (pinfunction "1_1") (pintype "passive"))
      (node (ref "R27") (pin "1") (pinfunction "1_1") (pintype "passive"))
    )
    (net (code "48") (name "Net-(IC3A--IN)") (class "Default")
      (node (ref "IC3") (pin "2") (pinfunction "-IN_2") (pintype "input"))
      (node (ref "R23") (pin "2") (pinfunction "2_2") (pintype "passive"))
      (node (ref "R24") (pin "1") (pinfunction "1_1") (pintype "passive"))
      (node (ref "R28") (pin "1") (pinfunction "1_1") (pintype "passive"))
    )
    (net (code "49") (name "Net-(IC3B-+IN)") (class "Default")
      (node (ref "IC3") (pin "5") (pinfunction "+IN_5") (pintype "input"))
      (node (ref "R20") (pin "1") (pinfunction "1_1") (pintype "passive"))
      (node (ref "R21") (pin "1") (pinfunction "1_1") (pintype "passive"))
    )
    (net (code "50") (name "Net-(IC3B--IN)") (class "Default")
      (node (ref "IC3") (pin "6") (pinfunction "-IN_6") (pintype "input"))
      (node (ref "R18") (pin "2") (pinfunction "2_2") (pintype "passive"))
      (node (ref "R19") (pin "1") (pinfunction "1_1") (pintype "passive"))
      (node (ref "R22") (pin "1") (pinfunction "1_1") (pintype "passive"))
    )
    (net (code "51") (name "Net-(IC3C-+IN)") (class "Default")
      (node (ref "IC3") (pin "10") (pinfunction "+IN_10") (pintype "input"))
      (node (ref "R38") (pin "1") (pinfunction "1_1") (pintype "passive"))
      (node (ref "R39") (pin "1") (pinfunction "1_1") (pintype "passive"))
      (node (ref "R40") (pin "1") (pinfunction "1_1") (pintype "passive"))
    )
    (net (code "52") (name "Net-(IC3C--IN)") (class "Default")
      (node (ref "IC3") (pin "9") (pinfunction "-IN_9") (pintype "input"))
      (node (ref "R36") (pin "2") (pinfunction "2_2") (pintype "passive"))
      (node (ref "R37") (pin "2") (pinfunction "2_2") (pintype "passive"))
      (node (ref "R41") (pin "1") (pinfunction "1_1") (pintype "passive"))
    )
    (net (code "53") (name "Net-(IC3D-+IN)") (class "Default")
      (node (ref "IC3") (pin "12") (pinfunction "+IN_12") (pintype "input"))
      (node (ref "R32") (pin "1") (pinfunction "1_1") (pintype "passive"))
      (node (ref "R33") (pin "1") (pinfunction "1_1") (pintype "passive"))
      (node (ref "R34") (pin "1") (pinfunction "1_1") (pintype "passive"))
    )
    (net (code "54") (name "Net-(IC3D--IN)") (class "Default")
      (node (ref "IC3") (pin "13") (pinfunction "-IN_13") (pintype "input"))
      (node (ref "R30") (pin "2") (pinfunction "2_2") (pintype "passive"))
      (node (ref "R31") (pin "2") (pinfunction "2_2") (pintype "passive"))
      (node (ref "R35") (pin "1") (pinfunction "1_1") (pintype "passive"))
    )
    (net (code "55") (name "Net-(IC4-VIN)") (class "Default")
      (node (ref "C25") (pin "1") (pinfunction "1_1") (pintype "passive"))
      (node (ref "IC4") (pin "3") (pinfunction "VIN_3") (pintype "input"))
      (node (ref "SJ4") (pin "1") (pinfunction "1_1") (pintype "passive"))
      (node (ref "SJ7") (pin "1") (pinfunction "1_1") (pintype "passive"))
    )
    (net (code "56") (name "Net-(LED1-PadC)") (class "Default")
      (node (ref "LED1") (pin "C") (pinfunction "C_C") (pintype "passive"))
      (node (ref "R14") (pin "2") (pinfunction "2_2") (pintype "passive"))
    )
    (net (code "57") (name "Net-(LED2-PadC)") (class "Default")
      (node (ref "LED2") (pin "C") (pinfunction "C_C") (pintype "passive"))
      (node (ref "R15") (pin "2") (pinfunction "2_2") (pintype "passive"))
    )
    (net (code "58") (name "Net-(LED3-PadC)") (class "Default")
      (node (ref "LED3") (pin "C") (pinfunction "C_C") (pintype "passive"))
      (node (ref "R16") (pin "2") (pinfunction "2_2") (pintype "passive"))
    )
    (net (code "59") (name "Net-(LED4-PadC)") (class "Default")
      (node (ref "LED4") (pin "C") (pinfunction "C_C") (pintype "passive"))
      (node (ref "R17") (pin "2") (pinfunction "2_2") (pintype "passive"))
    )
    (net (code "60") (name "Net-(LEVEL-3)") (class "Default")
      (node (ref "C17") (pin "1") (pinfunction "1_1") (pintype "passive"))
      (node (ref "LEVEL") (pin "N") (pinfunction "3_N") (pintype "passive"))
      (node (ref "R21") (pin "2") (pinfunction "2_2") (pintype "passive"))
    )
    (net (code "61") (name "Net-(OK1-A)") (class "Default")
      (node (ref "OK1") (pin "1") (pinfunction "A_1") (pintype "passive"))
      (node (ref "R5") (pin "2") (pinfunction "2_2") (pintype "passive"))
    )
    (net (code "62") (name "Net-(OK1-A2)") (class "Default")
      (node (ref "OK1") (pin "6") (pinfunction "A2_6") (pintype "passive"))
      (node (ref "R1") (pin "1") (pinfunction "1_1") (pintype "passive"))
    )
    (net (code "63") (name "Net-(OK2-A)") (class "Default")
      (node (ref "OK2") (pin "1") (pinfunction "A_1") (pintype "passive"))
      (node (ref "R6") (pin "2") (pinfunction "2_2") (pintype "passive"))
    )
    (net (code "64") (name "Net-(OK2-A2)") (class "Default")
      (node (ref "OK2") (pin "6") (pinfunction "A2_6") (pintype "passive"))
      (node (ref "R2") (pin "1") (pinfunction "1_1") (pintype "passive"))
    )
    (net (code "65") (name "Net-(OK3-A)") (class "Default")
      (node (ref "OK3") (pin "1") (pinfunction "A_1") (pintype "passive"))
      (node (ref "R7") (pin "2") (pinfunction "2_2") (pintype "passive"))
    )
    (net (code "66") (name "Net-(OK3-A2)") (class "Default")
      (node (ref "OK3") (pin "6") (pinfunction "A2_6") (pintype "passive"))
      (node (ref "R3") (pin "1") (pinfunction "1_1") (pintype "passive"))
    )
    (net (code "67") (name "Net-(OK4-A)") (class "Default")
      (node (ref "OK4") (pin "1") (pinfunction "A_1") (pintype "passive"))
      (node (ref "R8") (pin "2") (pinfunction "2_2") (pintype "passive"))
    )
    (net (code "68") (name "Net-(OK4-A2)") (class "Default")
      (node (ref "OK4") (pin "6") (pinfunction "A2_6") (pintype "passive"))
      (node (ref "R4") (pin "1") (pinfunction "1_1") (pintype "passive"))
    )
    (net (code "69") (name "Net-(OK5-A)") (class "Default")
      (node (ref "C26") (pin "1") (pinfunction "1_1") (pintype "passive"))
      (node (ref "OK5") (pin "1") (pinfunction "A_1") (pintype "passive"))
      (node (ref "R43") (pin "2") (pinfunction "2_2") (pintype "passive"))
    )
    (net (code "70") (name "Net-(OK5-C)") (class "Default")
      (node (ref "OK5") (pin "2") (pinfunction "C_2") (pintype "passive"))
      (node (ref "Q1") (pin "3") (pinfunction "D_3") (pintype "passive"))
    )
    (net (code "71") (name "Net-(PWRLED-1)") (class "Default")
      (node (ref "PWRLED") (pin "+") (pinfunction "1_+") (pintype "passive"))
      (node (ref "R12") (pin "2") (pinfunction "2_2") (pintype "passive"))
    )
    (net (code "72") (name "Net-(Q1-G)") (class "Default")
      (node (ref "D10") (pin "A") (pinfunction "A_A") (pintype "passive"))
      (node (ref "Q1") (pin "1") (pinfunction "G_1") (pintype "passive"))
      (node (ref "R9") (pin "1") (pinfunction "1_1") (pintype "passive"))
    )
    (net (code "73") (name "Net-(Q1-S)") (class "Default")
      (node (ref "Q1") (pin "2") (pinfunction "S_2") (pintype "passive"))
      (node (ref "R9") (pin "2") (pinfunction "2_2") (pintype "passive"))
    )
    (net (code "74") (name "Net-(Q2-D)") (class "Default")
      (node (ref "Q2") (pin "3") (pinfunction "D_3") (pintype "passive"))
      (node (ref "SG1") (pin "-") (pinfunction "2_-") (pintype "passive"))
    )
    (net (code "75") (name "Net-(R2-Pad2)") (class "Default")
      (node (ref "R2") (pin "2") (pinfunction "2_2") (pintype "passive"))
      (node (ref "T3") (pin "G") (pinfunction "G_G") (pintype "passive"))
    )
    (net (code "76") (name "Net-(R3-Pad2)") (class "Default")
      (node (ref "R3") (pin "2") (pinfunction "2_2") (pintype "passive"))
      (node (ref "T4") (pin "G") (pinfunction "G_G") (pintype "passive"))
    )
    (net (code "77") (name "Net-(R4-Pad2)") (class "Default")
      (node (ref "R4") (pin "2") (pinfunction "2_2") (pintype "passive"))
      (node (ref "T5") (pin "G") (pinfunction "G_G") (pintype "passive"))
    )
    (net (code "78") (name "Net-(RDYLED-1)") (class "Default")
      (node (ref "R13") (pin "2") (pinfunction "2_2") (pintype "passive"))
      (node (ref "RDYLED") (pin "+") (pinfunction "1_+") (pintype "passive"))
    )
    (net (code "79") (name "V+") (class "Default")
      (node (ref "ARDUINO") (pin "15") (pinfunction "VIN_15") (pintype "power_in"))
      (node (ref "C1") (pin "+") (pinfunction "+_+") (pintype "passive"))
      (node (ref "D3") (pin "C") (pinfunction "C_C") (pintype "passive"))
      (node (ref "D4") (pin "C") (pinfunction "C_C") (pintype "passive"))
    )
    (net (code "80") (name "VDD") (class "Default")
      (node (ref "C12") (pin "1") (pinfunction "1_1") (pintype "passive"))
      (node (ref "C5") (pin "1") (pinfunction "1_1") (pintype "passive"))
      (node (ref "D9") (pin "C") (pinfunction "C_C") (pintype "passive"))
      (node (ref "IC1") (pin "5") (pinfunction "OUT_5") (pintype "power_in"))
      (node (ref "IC3") (pin "4") (pinfunction "V+_4") (pintype "power_in"))
      (node (ref "POWER") (pin "VDD") (pinfunction "1_VDD") (pintype "passive"))
      (node (ref "SG1") (pin "+") (pinfunction "1_+") (pintype "passive"))
    )
    (net (code "81") (name "VSS") (class "Default")
      (node (ref "C13") (pin "1") (pinfunction "1_1") (pintype "passive"))
      (node (ref "C4") (pin "1") (pinfunction "1_1") (pintype "passive"))
      (node (ref "D8") (pin "A") (pinfunction "A_A") (pintype "passive"))
      (node (ref "IC3") (pin "11") (pinfunction "V-_11") (pintype "power_in"))
      (node (ref "POWER") (pin "VSS") (pinfunction "3_VSS") (pintype "passive"))
    )
    (net (code "82") (name "unconnected-(ARDUINO-3V3-Pad2)") (class "Default")
      (node (ref "ARDUINO") (pin "2") (pinfunction "3V3_2") (pintype "output"))
    )
    (net (code "83") (name "unconnected-(ARDUINO-RX0-Pad17)") (class "Default")
      (node (ref "ARDUINO") (pin "17") (pinfunction "RX0_17") (pintype "bidirectional"))
    )
    (net (code "84") (name "unconnected-(ARDUINO-TX1-Pad16)") (class "Default")
      (node (ref "ARDUINO") (pin "16") (pinfunction "TX1_16") (pintype "bidirectional"))
    )
    (net (code "85") (name "unconnected-(ARDUINO-~{RESET}-Pad13)") (class "Default")
      (node (ref "ARDUINO") (pin "13") (pinfunction "~{RESET}_13") (pintype "input"))
    )
    (net (code "86") (name "unconnected-(ARDUINO-~{RESET}-Pad18)") (class "Default")
      (node (ref "ARDUINO") (pin "18") (pinfunction "~{RESET}_18") (pintype "input"))
    )
  )
)
